# Main.net
KiCad netlist of a schematic drawn in Altium Designer
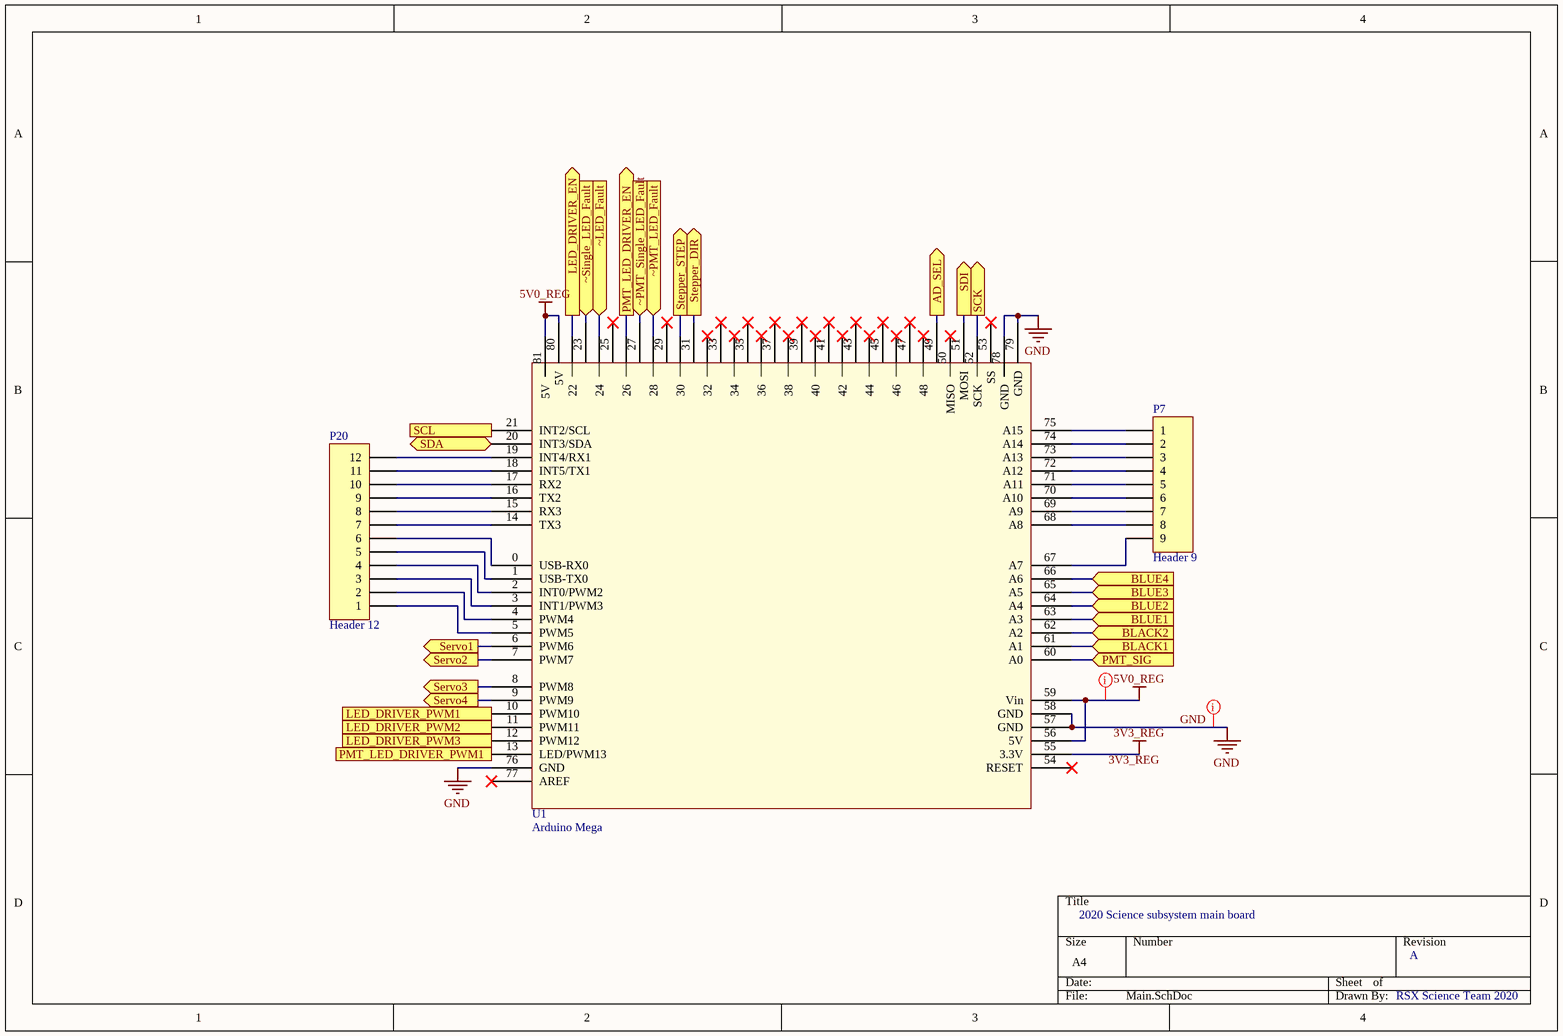
[diagram p0: Main.SchDoc]

(export (version "E")
  (design (tool "Eeschema 10.0.6"))
  (components
    (comp (ref "P7")
      (value "Header 9")
      (footprint "HDR1X9")
      (description "Header, 9-Pin")
      (fields (field (name "PUBLISHER") "Altium Limited"))
      (libsource (lib "Miscellaneous Connectors") (part "Header 9"))
    )
    (comp (ref "P20")
      (value "Header 12")
      (footprint "HDR1X12")
      (description "Header, 12-Pin")
      (fields (field (name "PUBLISHER") "Altium Limited"))
      (libsource (lib "Miscellaneous Connectors") (part "Header 12"))
    )
    (comp (ref "U1")
      (value "Arduino Mega")
      (footprint "Arduino Mega")
      (libsource (lib "RSX_Modules") (part "Arduino Mega"))
    )
  )
  (nets
    (net (code "1") (name "/AD_SEL") (class "Default")
      (node (ref "U1") (pin "49") (pinfunction "49_49") (pintype "passive"))
    )
    (net (code "2") (name "/BLACK1") (class "Default")
      (node (ref "U1") (pin "61") (pinfunction "A1_61") (pintype "passive"))
    )
    (net (code "3") (name "/BLACK2") (class "Default")
      (node (ref "U1") (pin "62") (pinfunction "A2_62") (pintype "passive"))
    )
    (net (code "4") (name "/BLUE1") (class "Default")
      (node (ref "U1") (pin "63") (pinfunction "A3_63") (pintype "passive"))
    )
    (net (code "5") (name "/BLUE2") (class "Default")
      (node (ref "U1") (pin "64") (pinfunction "A4_64") (pintype "passive"))
    )
    (net (code "6") (name "/BLUE3") (class "Default")
      (node (ref "U1") (pin "65") (pinfunction "A5_65") (pintype "passive"))
    )
    (net (code "7") (name "/BLUE4") (class "Default")
      (node (ref "U1") (pin "66") (pinfunction "A6_66") (pintype "passive"))
    )
    (net (code "8") (name "/LED_DRIVER_EN") (class "Default")
      (node (ref "U1") (pin "22") (pinfunction "22_22") (pintype "passive"))
    )
    (net (code "9") (name "/LED_DRIVER_PWM1") (class "Default")
      (node (ref "U1") (pin "10") (pinfunction "PWM10_10") (pintype "passive"))
    )
    (net (code "10") (name "/LED_DRIVER_PWM2") (class "Default")
      (node (ref "U1") (pin "11") (pinfunction "PWM11_11") (pintype "passive"))
    )
    (net (code "11") (name "/LED_DRIVER_PWM3") (class "Default")
      (node (ref "U1") (pin "12") (pinfunction "PWM12_12") (pintype "passive"))
    )
    (net (code "12") (name "/PMT_LED_DRIVER_EN") (class "Default")
      (node (ref "U1") (pin "26") (pinfunction "26_26") (pintype "passive"))
    )
    (net (code "13") (name "/PMT_LED_DRIVER_PWM1") (class "Default")
      (node (ref "U1") (pin "13") (pinfunction "LED/PWM13_13") (pintype "passive"))
    )
    (net (code "14") (name "/PMT_SIG") (class "Default")
      (node (ref "U1") (pin "60") (pinfunction "A0_60") (pintype "passive"))
    )
    (net (code "15") (name "/SCK") (class "Default")
      (node (ref "U1") (pin "52") (pinfunction "SCK_52") (pintype "passive"))
    )
    (net (code "16") (name "/SCL") (class "Default")
      (node (ref "U1") (pin "21") (pinfunction "INT2/SCL_21") (pintype "passive"))
    )
    (net (code "17") (name "/SDA") (class "Default")
      (node (ref "U1") (pin "20") (pinfunction "INT3/SDA_20") (pintype "passive"))
    )
    (net (code "18") (name "/SDI") (class "Default")
      (node (ref "U1") (pin "51") (pinfunction "MOSI_51") (pintype "passive"))
    )
    (net (code "19") (name "/Servo1") (class "Default")
      (node (ref "U1") (pin "6") (pinfunction "PWM6_6") (pintype "passive"))
    )
    (net (code "20") (name "/Servo2") (class "Default")
      (node (ref "U1") (pin "7") (pinfunction "PWM7_7") (pintype "passive"))
    )
    (net (code "21") (name "/Servo3") (class "Default")
      (node (ref "U1") (pin "8") (pinfunction "PWM8_8") (pintype "passive"))
    )
    (net (code "22") (name "/Servo4") (class "Default")
      (node (ref "U1") (pin "9") (pinfunction "PWM9_9") (pintype "passive"))
    )
    (net (code "23") (name "/Stepper_DIR") (class "Default")
      (node (ref "U1") (pin "31") (pinfunction "31_31") (pintype "passive"))
    )
    (net (code "24") (name "/Stepper_STEP") (class "Default")
      (node (ref "U1") (pin "30") (pinfunction "30_30") (pintype "passive"))
    )
    (net (code "25") (name "/~LED_Fault") (class "Default")
      (node (ref "U1") (pin "24") (pinfunction "24_24") (pintype "passive"))
    )
    (net (code "26") (name "/~PMT_LED_Fault") (class "Default")
      (node (ref "U1") (pin "28") (pinfunction "28_28") (pintype "passive"))
    )
    (net (code "27") (name "/~PMT_Single_LED_Fault") (class "Default")
      (node (ref "U1") (pin "27") (pinfunction "27_27") (pintype "passive"))
    )
    (net (code "28") (name "/~Single_LED_Fault") (class "Default")
      (node (ref "U1") (pin "23") (pinfunction "23_23") (pintype "passive"))
    )
    (net (code "29") (name "3V3_REG") (class "Default")
      (node (ref "U1") (pin "55") (pinfunction "3.3V_55") (pintype "passive"))
    )
    (net (code "30") (name "5V0_REG") (class "Default")
      (node (ref "U1") (pin "56") (pinfunction "5V_56") (pintype "passive"))
      (node (ref "U1") (pin "59") (pinfunction "Vin_59") (pintype "passive"))
      (node (ref "U1") (pin "80") (pinfunction "5V_80") (pintype "passive"))
      (node (ref "U1") (pin "81") (pinfunction "5V_81") (pintype "passive"))
    )
    (net (code "31") (name "GND") (class "Default")
      (node (ref "U1") (pin "57") (pinfunction "GND_57") (pintype "passive"))
      (node (ref "U1") (pin "58") (pinfunction "GND_58") (pintype "passive"))
      (node (ref "U1") (pin "76") (pinfunction "GND_76") (pintype "passive"))
      (node (ref "U1") (pin "78") (pinfunction "GND_78") (pintype "passive"))
      (node (ref "U1") (pin "79") (pinfunction "GND_79") (pintype "passive"))
    )
    (net (code "32") (name "Net-(U1-A7)") (class "Default")
      (node (ref "P7") (pin "9") (pinfunction "9_9") (pintype "passive"))
      (node (ref "U1") (pin "67") (pinfunction "A7_67") (pintype "passive"))
    )
    (net (code "33") (name "Net-(U1-A8)") (class "Default")
      (node (ref "P7") (pin "8") (pinfunction "8_8") (pintype "passive"))
      (node (ref "U1") (pin "68") (pinfunction "A8_68") (pintype "passive"))
    )
    (net (code "34") (name "Net-(U1-A9)") (class "Default")
      (node (ref "P7") (pin "7") (pinfunction "7_7") (pintype "passive"))
      (node (ref "U1") (pin "69") (pinfunction "A9_69") (pintype "passive"))
    )
    (net (code "35") (name "Net-(U1-A10)") (class "Default")
      (node (ref "P7") (pin "6") (pinfunction "6_6") (pintype "passive"))
      (node (ref "U1") (pin "70") (pinfunction "A10_70") (pintype "passive"))
    )
    (net (code "36") (name "Net-(U1-A11)") (class "Default")
      (node (ref "P7") (pin "5") (pinfunction "5_5") (pintype "passive"))
      (node (ref "U1") (pin "71") (pinfunction "A11_71") (pintype "passive"))
    )
    (net (code "37") (name "Net-(U1-A12)") (class "Default")
      (node (ref "P7") (pin "4") (pinfunction "4_4") (pintype "passive"))
      (node (ref "U1") (pin "72") (pinfunction "A12_72") (pintype "passive"))
    )
    (net (code "38") (name "Net-(U1-A13)") (class "Default")
      (node (ref "P7") (pin "3") (pinfunction "3_3") (pintype "passive"))
      (node (ref "U1") (pin "73") (pinfunction "A13_73") (pintype "passive"))
    )
    (net (code "39") (name "Net-(U1-A14)") (class "Default")
      (node (ref "P7") (pin "2") (pinfunction "2_2") (pintype "passive"))
      (node (ref "U1") (pin "74") (pinfunction "A14_74") (pintype "passive"))
    )
    (net (code "40") (name "Net-(U1-A15)") (class "Default")
      (node (ref "P7") (pin "1") (pinfunction "1_1") (pintype "passive"))
      (node (ref "U1") (pin "75") (pinfunction "A15_75") (pintype "passive"))
    )
    (net (code "41") (name "Net-(U1-INT0{slash}PWM2)") (class "Default")
      (node (ref "P20") (pin "4") (pinfunction "4_4") (pintype "passive"))
      (node (ref "U1") (pin "2") (pinfunction "INT0/PWM2_2") (pintype "passive"))
    )
    (net (code "42") (name "Net-(U1-INT1{slash}PWM3)") (class "Default")
      (node (ref "P20") (pin "3") (pinfunction "3_3") (pintype "passive"))
      (node (ref "U1") (pin "3") (pinfunction "INT1/PWM3_3") (pintype "passive"))
    )
    (net (code "43") (name "Net-(U1-INT4{slash}RX1)") (class "Default")
      (node (ref "P20") (pin "12") (pinfunction "12_12") (pintype "passive"))
      (node (ref "U1") (pin "19") (pinfunction "INT4/RX1_19") (pintype "passive"))
    )
    (net (code "44") (name "Net-(U1-INT5{slash}TX1)") (class "Default")
      (node (ref "P20") (pin "11") (pinfunction "11_11") (pintype "passive"))
      (node (ref "U1") (pin "18") (pinfunction "INT5/TX1_18") (pintype "passive"))
    )
    (net (code "45") (name "Net-(U1-PWM4)") (class "Default")
      (node (ref "P20") (pin "2") (pinfunction "2_2") (pintype "passive"))
      (node (ref "U1") (pin "4") (pinfunction "PWM4_4") (pintype "passive"))
    )
    (net (code "46") (name "Net-(U1-PWM5)") (class "Default")
      (node (ref "P20") (pin "1") (pinfunction "1_1") (pintype "passive"))
      (node (ref "U1") (pin "5") (pinfunction "PWM5_5") (pintype "passive"))
    )
    (net (code "47") (name "Net-(U1-RX2)") (class "Default")
      (node (ref "P20") (pin "10") (pinfunction "10_10") (pintype "passive"))
      (node (ref "U1") (pin "17") (pinfunction "RX2_17") (pintype "passive"))
    )
    (net (code "48") (name "Net-(U1-RX3)") (class "Default")
      (node (ref "P20") (pin "8") (pinfunction "8_8") (pintype "passive"))
      (node (ref "U1") (pin "15") (pinfunction "RX3_15") (pintype "passive"))
    )
    (net (code "49") (name "Net-(U1-TX2)") (class "Default")
      (node (ref "P20") (pin "9") (pinfunction "9_9") (pintype "passive"))
      (node (ref "U1") (pin "16") (pinfunction "TX2_16") (pintype "passive"))
    )
    (net (code "50") (name "Net-(U1-TX3)") (class "Default")
      (node (ref "P20") (pin "7") (pinfunction "7_7") (pintype "passive"))
      (node (ref "U1") (pin "14") (pinfunction "TX3_14") (pintype "passive"))
    )
    (net (code "51") (name "Net-(U1-USB-RX0)") (class "Default")
      (node (ref "P20") (pin "6") (pinfunction "6_6") (pintype "passive"))
      (node (ref "U1") (pin "0") (pinfunction "USB-RX0_0") (pintype "passive"))
    )
    (net (code "52") (name "Net-(U1-USB-TX0)") (class "Default")
      (node (ref "P20") (pin "5") (pinfunction "5_5") (pintype "passive"))
      (node (ref "U1") (pin "1") (pinfunction "USB-TX0_1") (pintype "passive"))
    )
    (net (code "53") (name "unconnected-(U1-AREF-Pad77)") (class "Default")
      (node (ref "U1") (pin "77") (pinfunction "AREF_77") (pintype "passive+no_connect"))
    )
    (net (code "54") (name "unconnected-(U1-MISO-Pad50)") (class "Default")
      (node (ref "U1") (pin "50") (pinfunction "MISO_50") (pintype "passive+no_connect"))
    )
    (net (code "55") (name "unconnected-(U1-Pad25)") (class "Default")
      (node (ref "U1") (pin "25") (pinfunction "25_25") (pintype "passive+no_connect"))
    )
    (net (code "56") (name "unconnected-(U1-Pad29)") (class "Default")
      (node (ref "U1") (pin "29") (pinfunction "29_29") (pintype "passive+no_connect"))
    )
    (net (code "57") (name "unconnected-(U1-Pad32)") (class "Default")
      (node (ref "U1") (pin "32") (pinfunction "32_32") (pintype "passive+no_connect"))
    )
    (net (code "58") (name "unconnected-(U1-Pad33)") (class "Default")
      (node (ref "U1") (pin "33") (pinfunction "33_33") (pintype "passive+no_connect"))
    )
    (net (code "59") (name "unconnected-(U1-Pad34)") (class "Default")
      (node (ref "U1") (pin "34") (pinfunction "34_34") (pintype "passive+no_connect"))
    )
    (net (code "60") (name "unconnected-(U1-Pad35)") (class "Default")
      (node (ref "U1") (pin "35") (pinfunction "35_35") (pintype "passive+no_connect"))
    )
    (net (code "61") (name "unconnected-(U1-Pad36)") (class "Default")
      (node (ref "U1") (pin "36") (pinfunction "36_36") (pintype "passive+no_connect"))
    )
    (net (code "62") (name "unconnected-(U1-Pad37)") (class "Default")
      (node (ref "U1") (pin "37") (pinfunction "37_37") (pintype "passive+no_connect"))
    )
    (net (code "63") (name "unconnected-(U1-Pad38)") (class "Default")
      (node (ref "U1") (pin "38") (pinfunction "38_38") (pintype "passive+no_connect"))
    )
    (net (code "64") (name "unconnected-(U1-Pad39)") (class "Default")
      (node (ref "U1") (pin "39") (pinfunction "39_39") (pintype "passive+no_connect"))
    )
    (net (code "65") (name "unconnected-(U1-Pad40)") (class "Default")
      (node (ref "U1") (pin "40") (pinfunction "40_40") (pintype "passive+no_connect"))
    )
    (net (code "66") (name "unconnected-(U1-Pad41)") (class "Default")
      (node (ref "U1") (pin "41") (pinfunction "41_41") (pintype "passive+no_connect"))
    )
    (net (code "67") (name "unconnected-(U1-Pad42)") (class "Default")
      (node (ref "U1") (pin "42") (pinfunction "42_42") (pintype "passive+no_connect"))
    )
    (net (code "68") (name "unconnected-(U1-Pad43)") (class "Default")
      (node (ref "U1") (pin "43") (pinfunction "43_43") (pintype "passive+no_connect"))
    )
    (net (code "69") (name "unconnected-(U1-Pad44)") (class "Default")
      (node (ref "U1") (pin "44") (pinfunction "44_44") (pintype "passive+no_connect"))
    )
    (net (code "70") (name "unconnected-(U1-Pad45)") (class "Default")
      (node (ref "U1") (pin "45") (pinfunction "45_45") (pintype "passive+no_connect"))
    )
    (net (code "71") (name "unconnected-(U1-Pad46)") (class "Default")
      (node (ref "U1") (pin "46") (pinfunction "46_46") (pintype "passive+no_connect"))
    )
    (net (code "72") (name "unconnected-(U1-Pad47)") (class "Default")
      (node (ref "U1") (pin "47") (pinfunction "47_47") (pintype "passive+no_connect"))
    )
    (net (code "73") (name "unconnected-(U1-Pad48)") (class "Default")
      (node (ref "U1") (pin "48") (pinfunction "48_48") (pintype "passive+no_connect"))
    )
    (net (code "74") (name "unconnected-(U1-RESET-Pad54)") (class "Default")
      (node (ref "U1") (pin "54") (pinfunction "RESET_54") (pintype "passive+no_connect"))
    )
    (net (code "75") (name "unconnected-(U1-SS-Pad53)") (class "Default")
      (node (ref "U1") (pin "53") (pinfunction "SS_53") (pintype "passive+no_connect"))
    )
  )
)
